# Rod_I2C_Extender_FFC.net
KiCad netlist of a schematic drawn in EAGLE
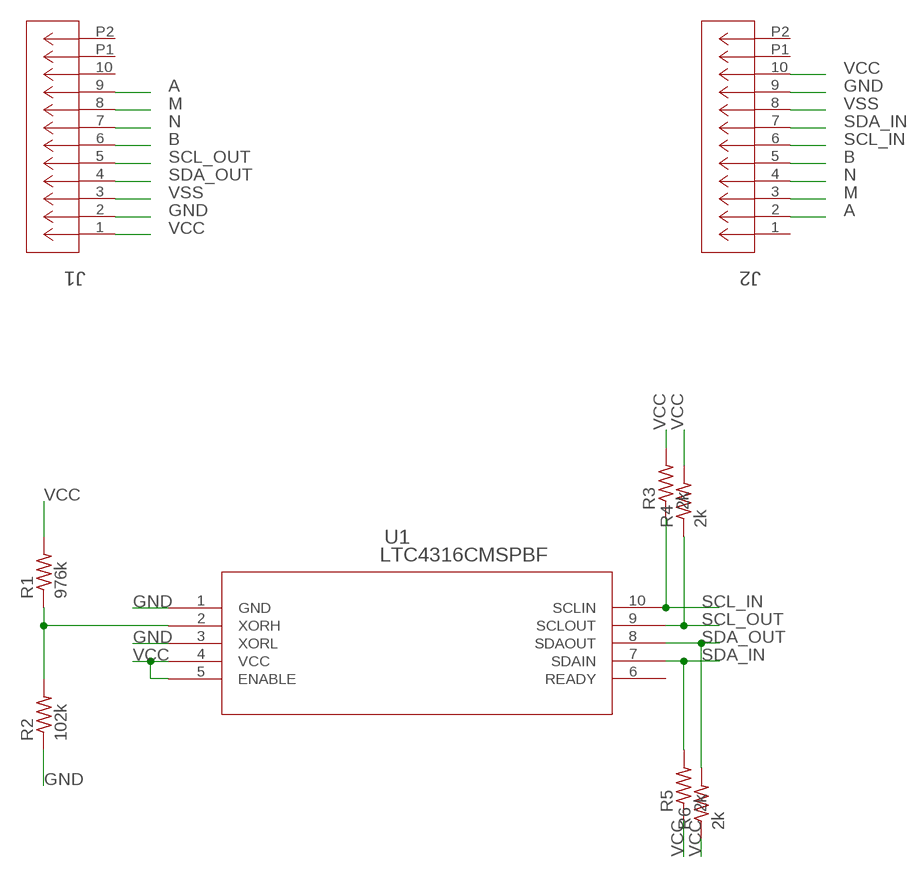
[diagram p0: schematic, sheet 1]

(export (version "E")
  (design (tool "Eeschema 10.0.6"))
  (components
    (comp (ref "J1")
      (value "522711079")
      (footprint "eagle-import:CON_522711079_MOL")
      (fields (field (name "COPYRIGHT") "Copyright (C) 2023 Ultra Librarian. All rights reserved."))
      (libsource (lib "eagle-import") (part "522711079"))
    )
    (comp (ref "J2")
      (value "522711079")
      (footprint "eagle-import:CON_522711079_MOL")
      (fields (field (name "COPYRIGHT") "Copyright (C) 2023 Ultra Librarian. All rights reserved."))
      (libsource (lib "eagle-import") (part "522711079"))
    )
    (comp (ref "R1")
      (value "976k")
      (footprint "eagle-import:R0603")
      (libsource (lib "eagle-import") (part "R-US_R0603"))
    )
    (comp (ref "R2")
      (value "102k")
      (footprint "eagle-import:R0603")
      (libsource (lib "eagle-import") (part "R-US_R0603"))
    )
    (comp (ref "R3")
      (value "2k")
      (footprint "eagle-import:R0603")
      (libsource (lib "eagle-import") (part "R-US_R0603"))
    )
    (comp (ref "R4")
      (value "2k")
      (footprint "eagle-import:R0603")
      (libsource (lib "eagle-import") (part "R-US_R0603"))
    )
    (comp (ref "R5")
      (value "2k")
      (footprint "eagle-import:R0603")
      (libsource (lib "eagle-import") (part "R-US_R0603"))
    )
    (comp (ref "R6")
      (value "2k")
      (footprint "eagle-import:R0603")
      (libsource (lib "eagle-import") (part "R-US_R0603"))
    )
    (comp (ref "U1")
      (value "LTC4316CMSPBF")
      (footprint "eagle-import:MSOP-10_MS")
      (fields (field (name "MF") "Analog Devices") (field (name "MP") "LTC4316CMS#PBF"))
      (libsource (lib "eagle-import") (part "LTC4316CMSPBF"))
    )
  )
  (nets
    (net (code "1") (name "/A") (class "Default")
      (node (ref "J1") (pin "9") (pinfunction "9_9") (pintype "passive"))
      (node (ref "J2") (pin "2") (pinfunction "2_2") (pintype "passive"))
    )
    (net (code "2") (name "/B") (class "Default")
      (node (ref "J1") (pin "6") (pinfunction "6_6") (pintype "passive"))
      (node (ref "J2") (pin "5") (pinfunction "5_5") (pintype "passive"))
    )
    (net (code "3") (name "/GND") (class "Default")
      (node (ref "J1") (pin "2") (pinfunction "2_2") (pintype "passive"))
      (node (ref "J2") (pin "9") (pinfunction "9_9") (pintype "passive"))
      (node (ref "R2") (pin "1") (pinfunction "1_1") (pintype "passive"))
      (node (ref "U1") (pin "1") (pinfunction "GND_1") (pintype "power_in"))
      (node (ref "U1") (pin "3") (pinfunction "XORL_3") (pintype "input"))
    )
    (net (code "4") (name "/M") (class "Default")
      (node (ref "J1") (pin "8") (pinfunction "8_8") (pintype "passive"))
      (node (ref "J2") (pin "3") (pinfunction "3_3") (pintype "passive"))
    )
    (net (code "5") (name "/N") (class "Default")
      (node (ref "J1") (pin "7") (pinfunction "7_7") (pintype "passive"))
      (node (ref "J2") (pin "4") (pinfunction "4_4") (pintype "passive"))
    )
    (net (code "6") (name "/SCL_IN") (class "Default")
      (node (ref "J2") (pin "6") (pinfunction "6_6") (pintype "passive"))
      (node (ref "R3") (pin "1") (pinfunction "1_1") (pintype "passive"))
      (node (ref "U1") (pin "10") (pinfunction "SCLIN_10") (pintype "bidirectional"))
    )
    (net (code "7") (name "/SCL_OUT") (class "Default")
      (node (ref "J1") (pin "5") (pinfunction "5_5") (pintype "passive"))
      (node (ref "R4") (pin "1") (pinfunction "1_1") (pintype "passive"))
      (node (ref "U1") (pin "9") (pinfunction "SCLOUT_9") (pintype "bidirectional"))
    )
    (net (code "8") (name "/SDA_IN") (class "Default")
      (node (ref "J2") (pin "7") (pinfunction "7_7") (pintype "passive"))
      (node (ref "R5") (pin "2") (pinfunction "2_2") (pintype "passive"))
      (node (ref "U1") (pin "7") (pinfunction "SDAIN_7") (pintype "bidirectional"))
    )
    (net (code "9") (name "/SDA_OUT") (class "Default")
      (node (ref "J1") (pin "4") (pinfunction "4_4") (pintype "passive"))
      (node (ref "R6") (pin "2") (pinfunction "2_2") (pintype "passive"))
      (node (ref "U1") (pin "8") (pinfunction "SDAOUT_8") (pintype "bidirectional"))
    )
    (net (code "10") (name "/VCC") (class "Default")
      (node (ref "J1") (pin "1") (pinfunction "1_1") (pintype "passive"))
      (node (ref "J2") (pin "10") (pinfunction "10_10") (pintype "passive"))
      (node (ref "R1") (pin "2") (pinfunction "2_2") (pintype "passive"))
      (node (ref "R3") (pin "2") (pinfunction "2_2") (pintype "passive"))
      (node (ref "R4") (pin "2") (pinfunction "2_2") (pintype "passive"))
      (node (ref "R5") (pin "1") (pinfunction "1_1") (pintype "passive"))
      (node (ref "R6") (pin "1") (pinfunction "1_1") (pintype "passive"))
      (node (ref "U1") (pin "4") (pinfunction "VCC_4") (pintype "power_in"))
      (node (ref "U1") (pin "5") (pinfunction "ENABLE_5") (pintype "input"))
    )
    (net (code "11") (name "/VSS") (class "Default")
      (node (ref "J1") (pin "3") (pinfunction "3_3") (pintype "passive"))
      (node (ref "J2") (pin "8") (pinfunction "8_8") (pintype "passive"))
    )
    (net (code "12") (name "Net-(U1-XORH)") (class "Default")
      (node (ref "R1") (pin "1") (pinfunction "1_1") (pintype "passive"))
      (node (ref "R2") (pin "2") (pinfunction "2_2") (pintype "passive"))
      (node (ref "U1") (pin "2") (pinfunction "XORH_2") (pintype "input"))
    )
    (net (code "13") (name "unconnected-(J1-Pad10)") (class "Default")
      (node (ref "J1") (pin "10") (pinfunction "10_10") (pintype "passive"))
    )
    (net (code "14") (name "unconnected-(J1-PadP1)") (class "Default")
      (node (ref "J1") (pin "P1") (pinfunction "P1_P1") (pintype "passive"))
    )
    (net (code "15") (name "unconnected-(J1-PadP2)") (class "Default")
      (node (ref "J1") (pin "P2") (pinfunction "P2_P2") (pintype "passive"))
    )
    (net (code "16") (name "unconnected-(J2-Pad1)") (class "Default")
      (node (ref "J2") (pin "1") (pinfunction "1_1") (pintype "passive"))
    )
    (net (code "17") (name "unconnected-(J2-PadP1)") (class "Default")
      (node (ref "J2") (pin "P1") (pinfunction "P1_P1") (pintype "passive"))
    )
    (net (code "18") (name "unconnected-(J2-PadP2)") (class "Default")
      (node (ref "J2") (pin "P2") (pinfunction "P2_P2") (pintype "passive"))
    )
    (net (code "19") (name "unconnected-(U1-READY-Pad6)") (class "Default")
      (node (ref "U1") (pin "6") (pinfunction "READY_6") (pintype "output"))
    )
  )
)
